# gui.net
KiCad netlist of a schematic drawn in Altium Designer
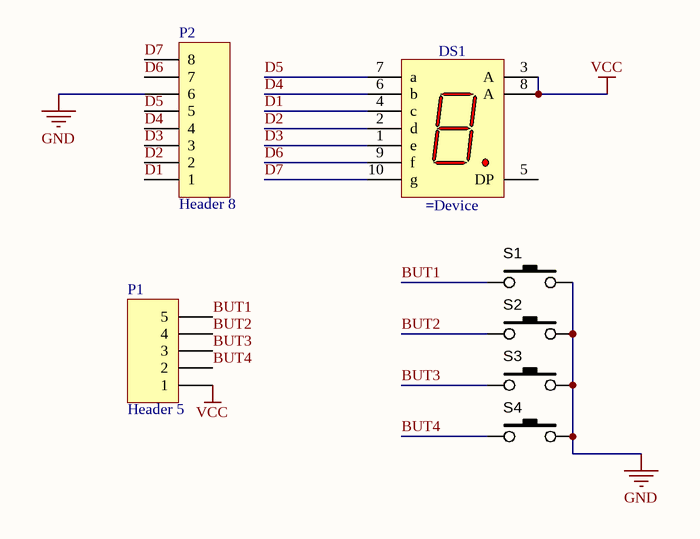
[diagram p0: gui.SchDoc]

(export (version "E")
  (design (tool "Eeschema 10.0.6"))
  (components
    (comp (ref "DS1")
      (value "~")
      (footprint "PCBComponent_1")
      (description "7-Segment Red Display Common Anode")
      (libsource (lib "LEDs & Displays") (part "7-Segment Red Display CA Type1"))
    )
    (comp (ref "P1")
      (value "Header 5")
      (footprint "HDR1X5")
      (description "Header, 5-Pin")
      (fields (field (name "PUBLISHER") "Altium Limited"))
      (libsource (lib "Miscellaneous Connectors") (part "Header 5"))
    )
    (comp (ref "P2")
      (value "Header 8")
      (footprint "HDR1X8")
      (description "Header, 8-Pin")
      (fields (field (name "PUBLISHER") "Altium Limited"))
      (libsource (lib "Miscellaneous Connectors") (part "Header 8"))
    )
    (comp (ref "S1")
      (value "SW_THT_PB_7.0mm")
      (footprint "TACT-SWITCH-TS1170")
      (description "Switch, tact, 7.0mm stem")
      (libsource (lib "PBL - Switches") (part "SW_THT_PB_7.0mm"))
    )
    (comp (ref "S2")
      (value "SW_THT_PB_7.0mm")
      (footprint "TACT-SWITCH-TS1170")
      (description "Switch, tact, 7.0mm stem")
      (libsource (lib "PBL - Switches") (part "SW_THT_PB_7.0mm"))
    )
    (comp (ref "S3")
      (value "SW_THT_PB_7.0mm")
      (footprint "TACT-SWITCH-TS1170")
      (description "Switch, tact, 7.0mm stem")
      (libsource (lib "PBL - Switches") (part "SW_THT_PB_7.0mm"))
    )
    (comp (ref "S4")
      (value "SW_THT_PB_7.0mm")
      (footprint "TACT-SWITCH-TS1170")
      (description "Switch, tact, 7.0mm stem")
      (libsource (lib "PBL - Switches") (part "SW_THT_PB_7.0mm"))
    )
  )
  (nets
    (net (code "1") (name "/BUT1") (class "Default")
      (node (ref "P1") (pin "5") (pinfunction "5_5") (pintype "passive"))
      (node (ref "S1") (pin "1") (pintype "passive"))
    )
    (net (code "2") (name "/BUT2") (class "Default")
      (node (ref "P1") (pin "4") (pinfunction "4_4") (pintype "passive"))
      (node (ref "S2") (pin "1") (pintype "passive"))
    )
    (net (code "3") (name "/BUT3") (class "Default")
      (node (ref "P1") (pin "3") (pinfunction "3_3") (pintype "passive"))
      (node (ref "S3") (pin "1") (pintype "passive"))
    )
    (net (code "4") (name "/BUT4") (class "Default")
      (node (ref "P1") (pin "2") (pinfunction "2_2") (pintype "passive"))
      (node (ref "S4") (pin "1") (pintype "passive"))
    )
    (net (code "5") (name "/D1") (class "Default")
      (node (ref "DS1") (pin "4") (pinfunction "c_4") (pintype "passive"))
      (node (ref "P2") (pin "1") (pinfunction "1_1") (pintype "passive"))
    )
    (net (code "6") (name "/D2") (class "Default")
      (node (ref "DS1") (pin "2") (pinfunction "d_2") (pintype "passive"))
      (node (ref "P2") (pin "2") (pinfunction "2_2") (pintype "passive"))
    )
    (net (code "7") (name "/D3") (class "Default")
      (node (ref "DS1") (pin "1") (pinfunction "e_1") (pintype "passive"))
      (node (ref "P2") (pin "3") (pinfunction "3_3") (pintype "passive"))
    )
    (net (code "8") (name "/D4") (class "Default")
      (node (ref "DS1") (pin "6") (pinfunction "b_6") (pintype "passive"))
      (node (ref "P2") (pin "4") (pinfunction "4_4") (pintype "passive"))
    )
    (net (code "9") (name "/D5") (class "Default")
      (node (ref "DS1") (pin "7") (pinfunction "a_7") (pintype "passive"))
      (node (ref "P2") (pin "5") (pinfunction "5_5") (pintype "passive"))
    )
    (net (code "10") (name "/D6") (class "Default")
      (node (ref "DS1") (pin "9") (pinfunction "f_9") (pintype "passive"))
      (node (ref "P2") (pin "7") (pinfunction "7_7") (pintype "passive"))
    )
    (net (code "11") (name "/D7") (class "Default")
      (node (ref "DS1") (pin "10") (pinfunction "g_10") (pintype "passive"))
      (node (ref "P2") (pin "8") (pinfunction "8_8") (pintype "passive"))
    )
    (net (code "12") (name "GND") (class "Default")
      (node (ref "P2") (pin "6") (pinfunction "6_6") (pintype "passive"))
      (node (ref "S1") (pin "2") (pintype "passive"))
      (node (ref "S2") (pin "2") (pintype "passive"))
      (node (ref "S3") (pin "2") (pintype "passive"))
      (node (ref "S4") (pin "2") (pintype "passive"))
    )
    (net (code "13") (name "VCC") (class "Default")
      (node (ref "DS1") (pin "3") (pinfunction "A_3") (pintype "passive"))
      (node (ref "DS1") (pin "8") (pinfunction "A_8") (pintype "passive"))
      (node (ref "P1") (pin "1") (pinfunction "1_1") (pintype "passive"))
    )
    (net (code "14") (name "unconnected-(DS1-DP-Pad5)") (class "Default")
      (node (ref "DS1") (pin "5") (pinfunction "DP_5") (pintype "passive"))
    )
  )
)
